# ProProject_GD32F103C8t6_2024-04-28.net
KiCad netlist of a schematic drawn in EasyEDA Pro
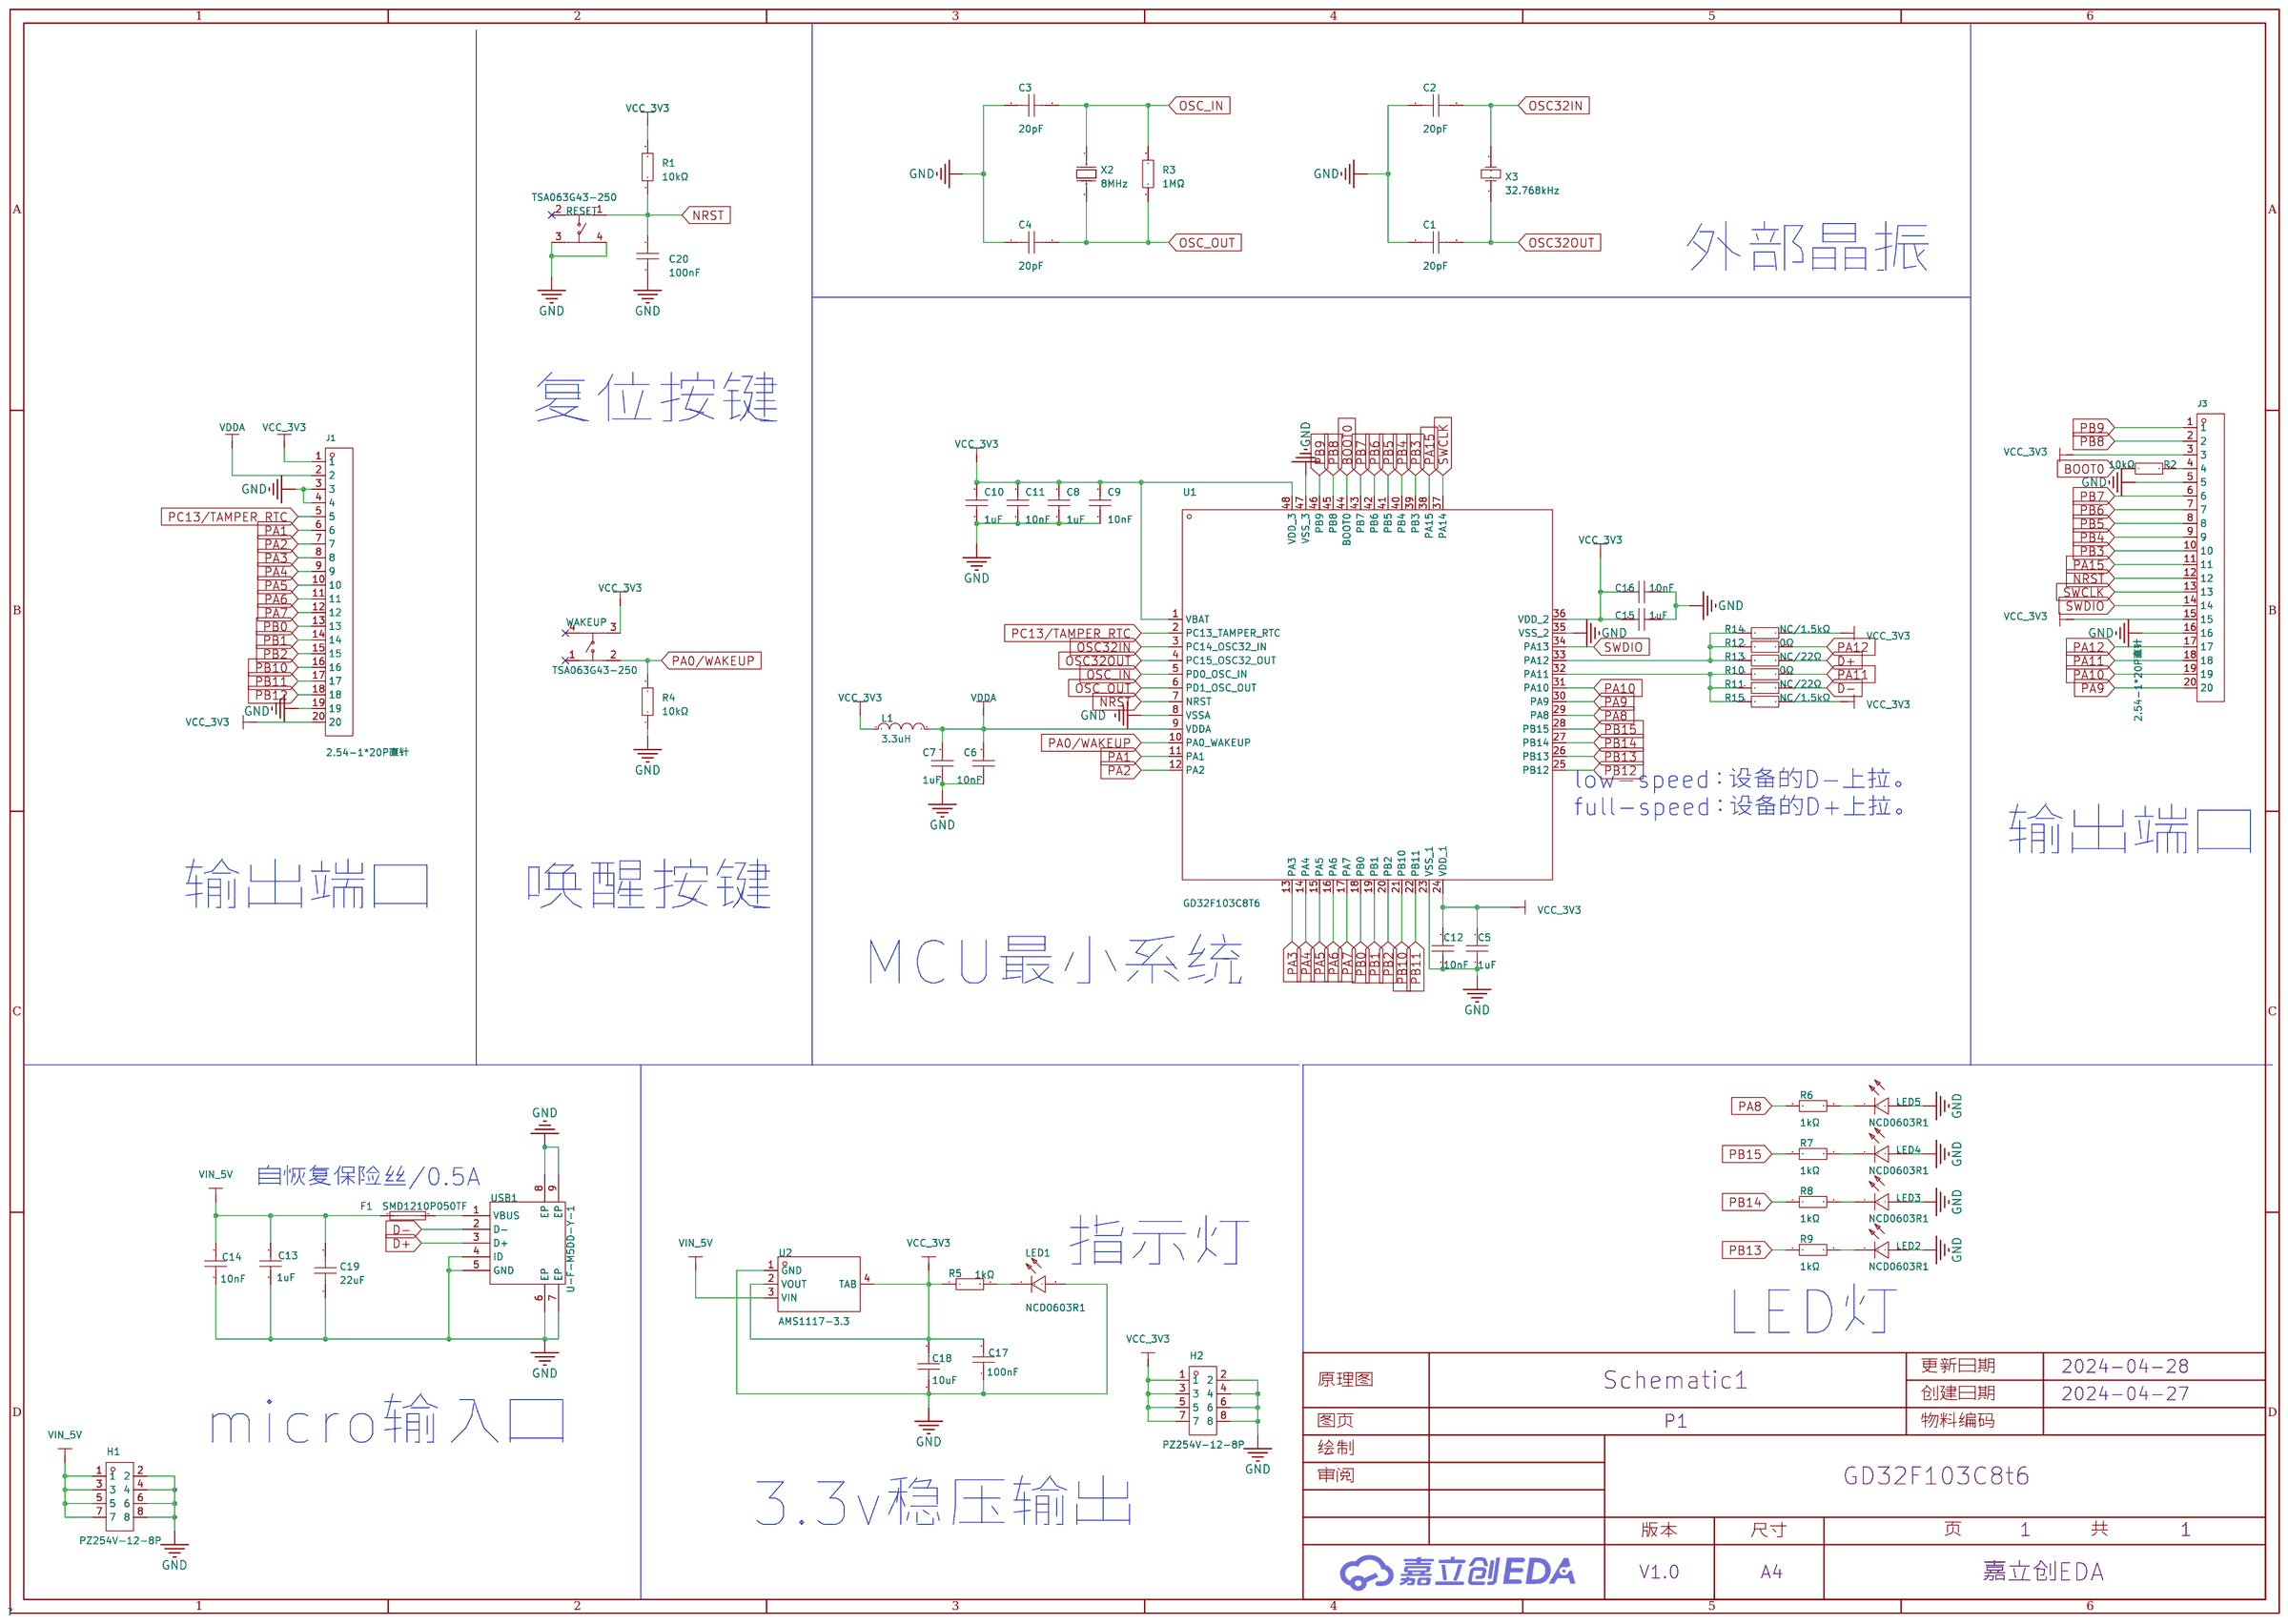
[diagram p0: schematic sheet]

(export (version "E")
  (design (tool "Eeschema 10.0.6"))
  (components
    (comp (ref "C1")
      (value "20pF")
      (footprint "easyedapro:C0603")
      (description "容值:20pF;精度:±5%;额定电压:50V;材质(温度系数):C0G;")
      (fields (field (name "Manufacturer Part") "0603CG200J500NT") (field (name "Manufacturer") "FH(风华)"))
      (libsource (lib "easyedapro") (part "0603CG200J500NT"))
    )
    (comp (ref "C2")
      (value "20pF")
      (footprint "easyedapro:C0603")
      (description "容值:20pF;精度:±5%;额定电压:50V;材质(温度系数):C0G;")
      (fields (field (name "Manufacturer Part") "0603CG200J500NT") (field (name "Manufacturer") "FH(风华)"))
      (libsource (lib "easyedapro") (part "0603CG200J500NT"))
    )
    (comp (ref "C3")
      (value "20pF")
      (footprint "easyedapro:C0603")
      (description "容值:20pF;精度:±5%;额定电压:50V;材质(温度系数):C0G;")
      (fields (field (name "Manufacturer Part") "0603CG200J500NT") (field (name "Manufacturer") "FH(风华)"))
      (libsource (lib "easyedapro") (part "0603CG200J500NT"))
    )
    (comp (ref "C4")
      (value "20pF")
      (footprint "easyedapro:C0603")
      (description "容值:20pF;精度:±5%;额定电压:50V;材质(温度系数):C0G;")
      (fields (field (name "Manufacturer Part") "0603CG200J500NT") (field (name "Manufacturer") "FH(风华)"))
      (libsource (lib "easyedapro") (part "0603CG200J500NT"))
    )
    (comp (ref "C5")
      (value "1uF")
      (footprint "easyedapro:C0603")
      (description "容值:1uF;精度:±10%;额定电压:10V;材质(温度系数):X5R;")
      (fields
        (field (name "Manufacturer Part") "CL10A105KP8NNNC")
        (field (name "Manufacturer") "SAMSUNG(三星)")
      )
      (libsource (lib "easyedapro") (part "CL10A105KP8NNNC"))
    )
    (comp (ref "C6")
      (value "10nF")
      (footprint "easyedapro:C0603")
      (description "容值:10nF;精度:±10%;额定电压:50V;材质(温度系数):X7R;")
      (fields
        (field (name "Manufacturer Part") "CC0603KRX7R9BB103")
        (field (name "Manufacturer") "YAGEO(国巨)")
      )
      (libsource (lib "easyedapro") (part "CC0603KRX7R9BB103"))
    )
    (comp (ref "C7")
      (value "1uF")
      (footprint "easyedapro:C0603")
      (description "容值:1uF;精度:±10%;额定电压:10V;材质(温度系数):X5R;")
      (fields
        (field (name "Manufacturer Part") "CL10A105KP8NNNC")
        (field (name "Manufacturer") "SAMSUNG(三星)")
      )
      (libsource (lib "easyedapro") (part "CL10A105KP8NNNC"))
    )
    (comp (ref "C8")
      (value "1uF")
      (footprint "easyedapro:C0603")
      (description "容值:1uF;精度:±10%;额定电压:10V;材质(温度系数):X5R;")
      (fields
        (field (name "Manufacturer Part") "CL10A105KP8NNNC")
        (field (name "Manufacturer") "SAMSUNG(三星)")
      )
      (libsource (lib "easyedapro") (part "CL10A105KP8NNNC"))
    )
    (comp (ref "C9")
      (value "10nF")
      (footprint "easyedapro:C0603")
      (description "容值:10nF;精度:±10%;额定电压:50V;材质(温度系数):X7R;")
      (fields
        (field (name "Manufacturer Part") "CC0603KRX7R9BB103")
        (field (name "Manufacturer") "YAGEO(国巨)")
      )
      (libsource (lib "easyedapro") (part "CC0603KRX7R9BB103"))
    )
    (comp (ref "C10")
      (value "1uF")
      (footprint "easyedapro:C0603")
      (description "容值:1uF;精度:±10%;额定电压:10V;材质(温度系数):X5R;")
      (fields
        (field (name "Manufacturer Part") "CL10A105KP8NNNC")
        (field (name "Manufacturer") "SAMSUNG(三星)")
      )
      (libsource (lib "easyedapro") (part "CL10A105KP8NNNC"))
    )
    (comp (ref "C11")
      (value "10nF")
      (footprint "easyedapro:C0603")
      (description "容值:10nF;精度:±10%;额定电压:50V;材质(温度系数):X7R;")
      (fields
        (field (name "Manufacturer Part") "CC0603KRX7R9BB103")
        (field (name "Manufacturer") "YAGEO(国巨)")
      )
      (libsource (lib "easyedapro") (part "CC0603KRX7R9BB103"))
    )
    (comp (ref "C12")
      (value "10nF")
      (footprint "easyedapro:C0603")
      (description "容值:10nF;精度:±10%;额定电压:50V;材质(温度系数):X7R;")
      (fields
        (field (name "Manufacturer Part") "CC0603KRX7R9BB103")
        (field (name "Manufacturer") "YAGEO(国巨)")
      )
      (libsource (lib "easyedapro") (part "CC0603KRX7R9BB103"))
    )
    (comp (ref "C13")
      (value "1uF")
      (footprint "easyedapro:C0603")
      (description "容值:1uF;精度:±10%;额定电压:10V;材质(温度系数):X5R;")
      (fields
        (field (name "Manufacturer Part") "CL10A105KP8NNNC")
        (field (name "Manufacturer") "SAMSUNG(三星)")
      )
      (libsource (lib "easyedapro") (part "CL10A105KP8NNNC"))
    )
    (comp (ref "C14")
      (value "10nF")
      (footprint "easyedapro:C0603")
      (description "容值:10nF;精度:±10%;额定电压:50V;材质(温度系数):X7R;")
      (fields
        (field (name "Manufacturer Part") "CC0603KRX7R9BB103")
        (field (name "Manufacturer") "YAGEO(国巨)")
      )
      (libsource (lib "easyedapro") (part "CC0603KRX7R9BB103"))
    )
    (comp (ref "C15")
      (value "1uF")
      (footprint "easyedapro:C0603")
      (description "容值:1uF;精度:±10%;额定电压:10V;材质(温度系数):X5R;")
      (fields
        (field (name "Manufacturer Part") "CL10A105KP8NNNC")
        (field (name "Manufacturer") "SAMSUNG(三星)")
      )
      (libsource (lib "easyedapro") (part "CL10A105KP8NNNC"))
    )
    (comp (ref "C16")
      (value "10nF")
      (footprint "easyedapro:C0603")
      (description "容值:10nF;精度:±10%;额定电压:50V;材质(温度系数):X7R;")
      (fields
        (field (name "Manufacturer Part") "CC0603KRX7R9BB103")
        (field (name "Manufacturer") "YAGEO(国巨)")
      )
      (libsource (lib "easyedapro") (part "CC0603KRX7R9BB103"))
    )
    (comp (ref "C17")
      (value "100nF")
      (footprint "easyedapro:C0603")
      (description "容值:100nF;精度:±10%;额定电压:50V;材质(温度系数):X7R;")
      (fields (field (name "Manufacturer Part") "0603B104K500NT") (field (name "Manufacturer") "FH(风华)"))
      (libsource (lib "easyedapro") (part "0603B104K500NT"))
    )
    (comp (ref "C18")
      (value "10uF")
      (footprint "easyedapro:C0805")
      (description "容值:10uF;精度:±10%;额定电压:25V;材质(温度系数):X5R;")
      (fields
        (field (name "Manufacturer Part") "CL21A106KAYNNNE")
        (field (name "Manufacturer") "SAMSUNG(三星)")
      )
      (libsource (lib "easyedapro") (part "CL21A106KAYNNNE"))
    )
    (comp (ref "C19")
      (value "22uF")
      (footprint "easyedapro:C0805")
      (description "容值:22uF;精度:±20%;额定电压:25V;材质(温度系数):X5R;")
      (fields
        (field (name "Manufacturer Part") "CL21A226MAQNNNE")
        (field (name "Manufacturer") "SAMSUNG(三星)")
      )
      (libsource (lib "easyedapro") (part "CL21A226MAQNNNE"))
    )
    (comp (ref "C20")
      (value "100nF")
      (footprint "easyedapro:C0603")
      (description "容值:100nF;精度:±10%;额定电压:50V;材质(温度系数):X7R;")
      (fields (field (name "Manufacturer Part") "0603B104K500NT") (field (name "Manufacturer") "FH(风华)"))
      (libsource (lib "easyedapro") (part "0603B104K500NT"))
    )
    (comp (ref "F1")
      (value "SMD1210P050TF")
      (footprint "easyedapro:F1210")
      (description "最大电压:13.2V;最大电流:100A;保持电流:500mA;跳闸电流:1A;")
      (fields (field (name "Manufacturer") "RUILON(瑞隆源)"))
      (libsource (lib "easyedapro") (part "SMD1210P050TF"))
    )
    (comp (ref "H1")
      (value "PZ254V-12-8P")
      (footprint "easyedapro:HDR-TH_8P-P2.54-V-M-R2-C4-S2.54")
      (fields (field (name "Manufacturer") "XFCN(兴飞)"))
      (libsource (lib "easyedapro") (part "PZ254V-12-8P"))
    )
    (comp (ref "H2")
      (value "PZ254V-12-8P")
      (footprint "easyedapro:HDR-TH_8P-P2.54-V-M-R2-C4-S2.54")
      (fields (field (name "Manufacturer") "XFCN(兴飞)"))
      (libsource (lib "easyedapro") (part "PZ254V-12-8P"))
    )
    (comp (ref "J1")
      (value "2.54-1*20P直针")
      (footprint "easyedapro:HDR-TH_20P-P2.54-V-M-1")
      (fields (field (name "Manufacturer") "BOOMELE(博穆精密)"))
      (libsource (lib "easyedapro") (part "Header-Male-2.54_1x20"))
    )
    (comp (ref "J3")
      (value "2.54-1*20P直针")
      (footprint "easyedapro:HDR-TH_20P-P2.54-V-M-1")
      (fields (field (name "Manufacturer") "BOOMELE(博穆精密)"))
      (libsource (lib "easyedapro") (part "Header-Male-2.54_1x20"))
    )
    (comp (ref "L1")
      (value "3.3uH")
      (footprint "easyedapro:L0603")
      (description "电感值:3.3uH;精度:±10%;额定电流:15mA;饱和电流(Isat):-;直流电阻(DCR):1Ω;")
      (fields (field (name "Manufacturer Part") "CMI160808U3R3KT") (field (name "Manufacturer") "FH(风华)"))
      (libsource (lib "easyedapro") (part "CMI160808U3R3KT"))
    )
    (comp (ref "LED1")
      (value "NCD0603R1")
      (footprint "easyedapro:LED0603-RD_RED")
      (fields (field (name "Manufacturer") "国星光电"))
      (libsource (lib "easyedapro") (part "FC-DA1608HRK-620D"))
    )
    (comp (ref "LED2")
      (value "NCD0603R1")
      (footprint "easyedapro:LED0603-RD_RED")
      (fields (field (name "Manufacturer") "国星光电"))
      (libsource (lib "easyedapro") (part "FC-DA1608HRK-620D"))
    )
    (comp (ref "LED3")
      (value "NCD0603R1")
      (footprint "easyedapro:LED0603-RD_RED")
      (fields (field (name "Manufacturer") "国星光电"))
      (libsource (lib "easyedapro") (part "FC-DA1608HRK-620D"))
    )
    (comp (ref "LED4")
      (value "NCD0603R1")
      (footprint "easyedapro:LED0603-RD_RED")
      (fields (field (name "Manufacturer") "国星光电"))
      (libsource (lib "easyedapro") (part "FC-DA1608HRK-620D"))
    )
    (comp (ref "LED5")
      (value "NCD0603R1")
      (footprint "easyedapro:LED0603-RD_RED")
      (fields (field (name "Manufacturer") "国星光电"))
      (libsource (lib "easyedapro") (part "FC-DA1608HRK-620D"))
    )
    (comp (ref "R1")
      (value "10kΩ")
      (footprint "easyedapro:R0603")
      (description "电阻类型:厚膜电阻;阻值:10kΩ;精度:±5%;功率:100mW;最大工作电压:75V;温度系数:±100ppm/°C;")
      (fields (field (name "Manufacturer Part") "RC0603JR-0710KL") (field (name "Manufacturer") "YAGEO(国巨)"))
      (libsource (lib "easyedapro") (part "RC0603JR-0710KL"))
    )
    (comp (ref "R2")
      (value "10kΩ")
      (footprint "easyedapro:R0603")
      (description "电阻类型:厚膜电阻;阻值:10kΩ;精度:±5%;功率:100mW;最大工作电压:75V;温度系数:±100ppm/°C;")
      (fields (field (name "Manufacturer Part") "RC0603JR-0710KL") (field (name "Manufacturer") "YAGEO(国巨)"))
      (libsource (lib "easyedapro") (part "RC0603JR-0710KL"))
    )
    (comp (ref "R3")
      (value "1MΩ")
      (footprint "easyedapro:R0603")
      (description "电阻类型:厚膜电阻;阻值:1MΩ;精度:±5%;功率:100mW;最大工作电压:75V;温度系数:±100ppm/°C;")
      (fields (field (name "Manufacturer Part") "RC0603JR-071ML") (field (name "Manufacturer") "YAGEO(国巨)"))
      (libsource (lib "easyedapro") (part "RC0603JR-071ML"))
    )
    (comp (ref "R4")
      (value "10kΩ")
      (footprint "easyedapro:R0603")
      (description "电阻类型:厚膜电阻;阻值:10kΩ;精度:±5%;功率:100mW;最大工作电压:75V;温度系数:±100ppm/°C;")
      (fields (field (name "Manufacturer Part") "RC0603JR-0710KL") (field (name "Manufacturer") "YAGEO(国巨)"))
      (libsource (lib "easyedapro") (part "RC0603JR-0710KL"))
    )
    (comp (ref "R5")
      (value "1kΩ")
      (footprint "easyedapro:R0603")
      (description "电阻类型:薄膜电阻;阻值:1kΩ;精度:±0.1%;功率:100mW;最大工作电压:75V;温度系数:±25ppm/°C;")
      (fields (field (name "Manufacturer Part") "RT0603BRD071KL") (field (name "Manufacturer") "YAGEO(国巨)"))
      (libsource (lib "easyedapro") (part "RT0603BRD071KL"))
    )
    (comp (ref "R6")
      (value "1kΩ")
      (footprint "easyedapro:R0603")
      (description "电阻类型:薄膜电阻;阻值:1kΩ;精度:±0.1%;功率:100mW;最大工作电压:75V;温度系数:±25ppm/°C;")
      (fields (field (name "Manufacturer Part") "RT0603BRD071KL") (field (name "Manufacturer") "YAGEO(国巨)"))
      (libsource (lib "easyedapro") (part "RT0603BRD071KL"))
    )
    (comp (ref "R7")
      (value "1kΩ")
      (footprint "easyedapro:R0603")
      (description "电阻类型:薄膜电阻;阻值:1kΩ;精度:±0.1%;功率:100mW;最大工作电压:75V;温度系数:±25ppm/°C;")
      (fields (field (name "Manufacturer Part") "RT0603BRD071KL") (field (name "Manufacturer") "YAGEO(国巨)"))
      (libsource (lib "easyedapro") (part "RT0603BRD071KL"))
    )
    (comp (ref "R8")
      (value "1kΩ")
      (footprint "easyedapro:R0603")
      (description "电阻类型:薄膜电阻;阻值:1kΩ;精度:±0.1%;功率:100mW;最大工作电压:75V;温度系数:±25ppm/°C;")
      (fields (field (name "Manufacturer Part") "RT0603BRD071KL") (field (name "Manufacturer") "YAGEO(国巨)"))
      (libsource (lib "easyedapro") (part "RT0603BRD071KL"))
    )
    (comp (ref "R9")
      (value "1kΩ")
      (footprint "easyedapro:R0603")
      (description "电阻类型:薄膜电阻;阻值:1kΩ;精度:±0.1%;功率:100mW;最大工作电压:75V;温度系数:±25ppm/°C;")
      (fields (field (name "Manufacturer Part") "RT0603BRD071KL") (field (name "Manufacturer") "YAGEO(国巨)"))
      (libsource (lib "easyedapro") (part "RT0603BRD071KL"))
    )
    (comp (ref "R10")
      (value "0Ω")
      (footprint "easyedapro:R0603")
      (description "电阻类型:厚膜电阻;阻值:1.5kΩ;精度:±1%;功率:100mW;最大工作电压:50V;温度系数:±100ppm/°C;")
      (fields
        (field (name "Manufacturer Part") "0603WAJ0000T5E")
        (field (name "Manufacturer") "UNI-ROYAL(厚声)")
      )
      (libsource (lib "easyedapro") (part "RS-03K1501FT"))
    )
    (comp (ref "R11")
      (value "NC/22Ω")
      (footprint "easyedapro:R0603")
      (description "电阻类型:厚膜电阻;阻值:22Ω;精度:±1%;功率:100mW;最大工作电压:50V;温度系数:±100ppm/°C;")
      (fields (field (name "Manufacturer Part") "RS-03K22R0FT") (field (name "Manufacturer") "FH(风华)"))
      (libsource (lib "easyedapro") (part "RS-03K22R0FT"))
    )
    (comp (ref "R12")
      (value "0Ω")
      (footprint "easyedapro:R0603")
      (description "电阻类型:厚膜电阻;阻值:1.5kΩ;精度:±1%;功率:100mW;最大工作电压:50V;温度系数:±100ppm/°C;")
      (fields
        (field (name "Manufacturer Part") "0603WAJ0000T5E")
        (field (name "Manufacturer") "UNI-ROYAL(厚声)")
      )
      (libsource (lib "easyedapro") (part "RS-03K1501FT"))
    )
    (comp (ref "R13")
      (value "NC/22Ω")
      (footprint "easyedapro:R0603")
      (description "电阻类型:厚膜电阻;阻值:22Ω;精度:±1%;功率:100mW;最大工作电压:50V;温度系数:±100ppm/°C;")
      (fields (field (name "Manufacturer Part") "RS-03K22R0FT") (field (name "Manufacturer") "FH(风华)"))
      (libsource (lib "easyedapro") (part "RS-03K22R0FT"))
    )
    (comp (ref "R14")
      (value "NC/1.5kΩ")
      (footprint "easyedapro:R0603")
      (description "电阻类型:厚膜电阻;阻值:1.5kΩ;精度:±1%;功率:100mW;最大工作电压:50V;温度系数:±100ppm/°C;")
      (fields (field (name "Manufacturer Part") "RS-03K1501FT") (field (name "Manufacturer") "FH(风华)"))
      (libsource (lib "easyedapro") (part "RS-03K1501FT"))
    )
    (comp (ref "R15")
      (value "NC/1.5kΩ")
      (footprint "easyedapro:R0603")
      (description "电阻类型:厚膜电阻;阻值:1.5kΩ;精度:±1%;功率:100mW;最大工作电压:50V;温度系数:±100ppm/°C;")
      (fields (field (name "Manufacturer Part") "RS-03K1501FT") (field (name "Manufacturer") "FH(风华)"))
      (libsource (lib "easyedapro") (part "RS-03K1501FT"))
    )
    (comp (ref "RESET")
      (value "TSA063G43-250")
      (footprint "easyedapro:KEY-SMD_4P-L6.0-W6.0-P4.50-LS10.0")
      (fields (field (name "Manufacturer") "BRIGHT(博瑞泰)"))
      (libsource (lib "easyedapro") (part "TSA063G43-250"))
    )
    (comp (ref "U1")
      (value "GD32F103C8T6")
      (footprint "easyedapro:TQFP-48_L7.0-W7.0-P0.50-LS9.0-BL")
      (description "CPU内核:CM3;程序存储容量:64KB;RAM总容量:20KB;GPIO端口数量:37;工作电压范围:2.6V~3.6V;CPU最大主频:108MHz;程序存储器类型:FLASH;")
      (fields (field (name "Manufacturer") "GigaDevice(兆易创新)"))
      (libsource (lib "easyedapro") (part "GD32F103C8T6"))
    )
    (comp (ref "U2")
      (value "AMS1117-3.3")
      (footprint "easyedapro:SOT-223-3_L6.5-W3.5-P3.05-LS7.0")
      (description "输出类型：固定 输出极性：正 最大输入电压：18V 输出电压：3.3V 输出电流：1A 电源纹波抑制比(PSRR)：60dB@(120Hz)。当前应用较多领域：三端稳压器，机顶盒")
      (fields (field (name "Manufacturer") "TWGMC(台湾迪嘉)"))
      (libsource (lib "easyedapro") (part "AMS1117-3.3_C5250992"))
    )
    (comp (ref "USB1")
      (value "U-F-M5DD-Y-1")
      (footprint "easyedapro:MICRO-USB-SMD_U-F-M5DD-Y-1")
      (description "连接器类型:Micro-B;标准:USB 2.0;公母:母;端口数量:1;触点数量:5P;额定电流 - 电源:1A;")
      (fields (field (name "Manufacturer") "韩国韩荣"))
      (libsource (lib "easyedapro") (part "U-F-M5DD-Y-1"))
    )
    (comp (ref "WAKEUP")
      (value "TSA063G43-250")
      (footprint "easyedapro:KEY-SMD_4P-L6.0-W6.0-P4.50-LS10.0")
      (fields (field (name "Manufacturer") "BRIGHT(博瑞泰)"))
      (libsource (lib "easyedapro") (part "TSA063G43-250"))
    )
    (comp (ref "X2")
      (value "8MHz")
      (footprint "easyedapro:OSC-TH_L10.0-W4.5-P5.00")
      (description "晶振类型:直插晶振;频率:8MHz;常温频差:±20ppm;外接负载电容:20pF;频率稳定度(全温):±30ppm;")
      (fields (field (name "Manufacturer Part") "X49SD8MSD2SC") (field (name "Manufacturer") "YXC(扬兴晶振)"))
      (libsource (lib "easyedapro") (part "X49SD8MSD2SC"))
    )
    (comp (ref "X3")
      (value "32.768kHz")
      (footprint "easyedapro:OSC-TH_BD3.1-P0.8-D0.3")
      (description "晶振类型:直插晶振;频率:32.768kHz;常温频差:±10ppm;外接负载电容:12.5pF;频率稳定度(全温):-;")
      (fields (field (name "Manufacturer Part") "X308032768KGB2SC") (field (name "Manufacturer") "YXC(扬兴晶振)"))
      (libsource (lib "easyedapro") (part "X308032768KGB2SC"))
    )
  )
  (nets
    (net (code "1") (name "BOOT0") (class "Default")
      (node (ref "R2") (pin "1") (pinfunction "1_1") (pintype "input"))
      (node (ref "U1") (pin "44") (pinfunction "BOOT0_44") (pintype "unspecified"))
    )
    (net (code "2") (name "D+") (class "Default")
      (node (ref "R13") (pin "2") (pinfunction "2_2") (pintype "unspecified"))
      (node (ref "USB1") (pin "3") (pinfunction "D+_3") (pintype "unspecified"))
    )
    (net (code "3") (name "D-") (class "Default")
      (node (ref "R11") (pin "2") (pinfunction "2_2") (pintype "unspecified"))
      (node (ref "USB1") (pin "2") (pinfunction "D-_2") (pintype "unspecified"))
    )
    (net (code "4") (name "GND") (class "Default")
      (node (ref "C1") (pin "1") (pinfunction "1_1") (pintype "unspecified"))
      (node (ref "C10") (pin "1") (pinfunction "1_1") (pintype "input"))
      (node (ref "C11") (pin "1") (pinfunction "1_1") (pintype "input"))
      (node (ref "C12") (pin "1") (pinfunction "1_1") (pintype "input"))
      (node (ref "C13") (pin "1") (pinfunction "1_1") (pintype "input"))
      (node (ref "C14") (pin "1") (pinfunction "1_1") (pintype "input"))
      (node (ref "C15") (pin "1") (pinfunction "1_1") (pintype "input"))
      (node (ref "C16") (pin "1") (pinfunction "1_1") (pintype "input"))
      (node (ref "C17") (pin "1") (pinfunction "1_1") (pintype "input"))
      (node (ref "C18") (pin "1") (pinfunction "1_1") (pintype "unspecified"))
      (node (ref "C19") (pin "1") (pinfunction "1_1") (pintype "unspecified"))
      (node (ref "C2") (pin "1") (pinfunction "1_1") (pintype "unspecified"))
      (node (ref "C20") (pin "1") (pinfunction "1_1") (pintype "input"))
      (node (ref "C3") (pin "1") (pinfunction "1_1") (pintype "unspecified"))
      (node (ref "C4") (pin "1") (pinfunction "1_1") (pintype "unspecified"))
      (node (ref "C5") (pin "1") (pinfunction "1_1") (pintype "input"))
      (node (ref "C6") (pin "1") (pinfunction "1_1") (pintype "input"))
      (node (ref "C7") (pin "1") (pinfunction "1_1") (pintype "input"))
      (node (ref "C8") (pin "1") (pinfunction "1_1") (pintype "input"))
      (node (ref "C9") (pin "1") (pinfunction "1_1") (pintype "input"))
      (node (ref "H1") (pin "2") (pinfunction "2_2") (pintype "unspecified"))
      (node (ref "H1") (pin "4") (pinfunction "4_4") (pintype "unspecified"))
      (node (ref "H1") (pin "6") (pinfunction "6_6") (pintype "unspecified"))
      (node (ref "H1") (pin "8") (pinfunction "8_8") (pintype "unspecified"))
      (node (ref "H2") (pin "2") (pinfunction "2_2") (pintype "unspecified"))
      (node (ref "H2") (pin "4") (pinfunction "4_4") (pintype "unspecified"))
      (node (ref "H2") (pin "6") (pinfunction "6_6") (pintype "unspecified"))
      (node (ref "H2") (pin "8") (pinfunction "8_8") (pintype "unspecified"))
      (node (ref "J1") (pin "19") (pinfunction "19_19") (pintype "input"))
      (node (ref "J1") (pin "3") (pinfunction "3_3") (pintype "input"))
      (node (ref "J1") (pin "4") (pinfunction "4_4") (pintype "input"))
      (node (ref "J3") (pin "16") (pinfunction "16_16") (pintype "input"))
      (node (ref "J3") (pin "5") (pinfunction "5_5") (pintype "input"))
      (node (ref "LED1") (pin "2") (pinfunction "A_2") (pintype "input"))
      (node (ref "LED2") (pin "2") (pinfunction "A_2") (pintype "input"))
      (node (ref "LED3") (pin "2") (pinfunction "A_2") (pintype "input"))
      (node (ref "LED4") (pin "2") (pinfunction "A_2") (pintype "input"))
      (node (ref "LED5") (pin "2") (pinfunction "A_2") (pintype "input"))
      (node (ref "R4") (pin "1") (pinfunction "1_1") (pintype "input"))
      (node (ref "RESET") (pin "3") (pinfunction "3_3") (pintype "input"))
      (node (ref "RESET") (pin "4") (pinfunction "4_4") (pintype "input"))
      (node (ref "U1") (pin "23") (pinfunction "VSS_1_23") (pintype "unspecified"))
      (node (ref "U1") (pin "35") (pinfunction "VSS_2_35") (pintype "unspecified"))
      (node (ref "U1") (pin "47") (pinfunction "VSS_3_47") (pintype "unspecified"))
      (node (ref "U1") (pin "8") (pinfunction "VSSA_8") (pintype "unspecified"))
      (node (ref "U2") (pin "1") (pinfunction "GND_1") (pintype "unspecified"))
      (node (ref "USB1") (pin "4") (pinfunction "ID_4") (pintype "unspecified"))
      (node (ref "USB1") (pin "5") (pinfunction "GND_5") (pintype "unspecified"))
      (node (ref "USB1") (pin "6") (pinfunction "EP_6") (pintype "unspecified"))
      (node (ref "USB1") (pin "7") (pinfunction "EP_7") (pintype "unspecified"))
      (node (ref "USB1") (pin "8") (pinfunction "EP_8") (pintype "unspecified"))
      (node (ref "USB1") (pin "9") (pinfunction "EP_9") (pintype "unspecified"))
    )
    (net (code "5") (name "NRST") (class "Default")
      (node (ref "C20") (pin "2") (pinfunction "2_2") (pintype "input"))
      (node (ref "J3") (pin "12") (pinfunction "12_12") (pintype "input"))
      (node (ref "R1") (pin "1") (pinfunction "1_1") (pintype "input"))
      (node (ref "RESET") (pin "1") (pinfunction "1_1") (pintype "input"))
      (node (ref "U1") (pin "7") (pinfunction "NRST_7") (pintype "unspecified"))
    )
    (net (code "6") (name "Net-(J3-Pad4)") (class "Default")
      (node (ref "J3") (pin "4") (pinfunction "4_4") (pintype "input"))
      (node (ref "R2") (pin "2") (pinfunction "2_2") (pintype "input"))
    )
    (net (code "7") (name "Net-(LED1-K)") (class "Default")
      (node (ref "LED1") (pin "1") (pinfunction "K_1") (pintype "input"))
      (node (ref "R5") (pin "2") (pinfunction "2_2") (pintype "input"))
    )
    (net (code "8") (name "Net-(LED2-K)") (class "Default")
      (node (ref "LED2") (pin "1") (pinfunction "K_1") (pintype "input"))
      (node (ref "R9") (pin "2") (pinfunction "2_2") (pintype "input"))
    )
    (net (code "9") (name "Net-(LED3-K)") (class "Default")
      (node (ref "LED3") (pin "1") (pinfunction "K_1") (pintype "input"))
      (node (ref "R8") (pin "2") (pinfunction "2_2") (pintype "input"))
    )
    (net (code "10") (name "Net-(LED4-K)") (class "Default")
      (node (ref "LED4") (pin "1") (pinfunction "K_1") (pintype "input"))
      (node (ref "R7") (pin "2") (pinfunction "2_2") (pintype "input"))
    )
    (net (code "11") (name "Net-(LED5-K)") (class "Default")
      (node (ref "LED5") (pin "1") (pinfunction "K_1") (pintype "input"))
      (node (ref "R6") (pin "2") (pinfunction "2_2") (pintype "input"))
    )
    (net (code "12") (name "Net-(U1-PA11)") (class "Default")
      (node (ref "R10") (pin "1") (pinfunction "1_1") (pintype "unspecified"))
      (node (ref "R11") (pin "1") (pinfunction "1_1") (pintype "unspecified"))
      (node (ref "R15") (pin "1") (pinfunction "1_1") (pintype "unspecified"))
      (node (ref "U1") (pin "32") (pinfunction "PA11_32") (pintype "unspecified"))
    )
    (net (code "13") (name "Net-(U1-PA12)") (class "Default")
      (node (ref "R12") (pin "1") (pinfunction "1_1") (pintype "unspecified"))
      (node (ref "R13") (pin "1") (pinfunction "1_1") (pintype "unspecified"))
      (node (ref "R14") (pin "1") (pinfunction "1_1") (pintype "unspecified"))
      (node (ref "U1") (pin "33") (pinfunction "PA12_33") (pintype "unspecified"))
    )
    (net (code "14") (name "Net-(USB1-VBUS)") (class "Default")
      (node (ref "F1") (pin "2") (pinfunction "2_2") (pintype "unspecified"))
      (node (ref "USB1") (pin "1") (pinfunction "VBUS_1") (pintype "unspecified"))
    )
    (net (code "15") (name "OSC32IN") (class "Default")
      (node (ref "C2") (pin "2") (pinfunction "2_2") (pintype "unspecified"))
      (node (ref "U1") (pin "3") (pinfunction "PC14_OSC32_IN_3") (pintype "unspecified"))
      (node (ref "X3") (pin "2") (pinfunction "OSC2_2") (pintype "unspecified"))
    )
    (net (code "16") (name "OSC32OUT") (class "Default")
      (node (ref "C1") (pin "2") (pinfunction "2_2") (pintype "unspecified"))
      (node (ref "U1") (pin "4") (pinfunction "PC15_OSC32_OUT_4") (pintype "unspecified"))
      (node (ref "X3") (pin "1") (pinfunction "OSC1_1") (pintype "unspecified"))
    )
    (net (code "17") (name "OSC_IN") (class "Default")
      (node (ref "C3") (pin "2") (pinfunction "2_2") (pintype "unspecified"))
      (node (ref "R3") (pin "2") (pinfunction "2_2") (pintype "input"))
      (node (ref "U1") (pin "5") (pinfunction "PD0_OSC_IN_5") (pintype "unspecified"))
      (node (ref "X2") (pin "1") (pinfunction "OSC1_1") (pintype "input"))
    )
    (net (code "18") (name "OSC_OUT") (class "Default")
      (node (ref "C4") (pin "2") (pinfunction "2_2") (pintype "unspecified"))
      (node (ref "R3") (pin "1") (pinfunction "1_1") (pintype "input"))
      (node (ref "U1") (pin "6") (pinfunction "PD1_OSC_OUT_6") (pintype "unspecified"))
      (node (ref "X2") (pin "2") (pinfunction "OSC2_2") (pintype "input"))
    )
    (net (code "19") (name "PA0{slash}WAKEUP") (class "Default")
      (node (ref "R4") (pin "2") (pinfunction "2_2") (pintype "input"))
      (node (ref "U1") (pin "10") (pinfunction "PA0_WAKEUP_10") (pintype "unspecified"))
      (node (ref "WAKEUP") (pin "2") (pinfunction "2_2") (pintype "input"))
    )
    (net (code "20") (name "PA1") (class "Default")
      (node (ref "J1") (pin "6") (pinfunction "6_6") (pintype "input"))
      (node (ref "U1") (pin "11") (pinfunction "PA1_11") (pintype "unspecified"))
    )
    (net (code "21") (name "PA2") (class "Default")
      (node (ref "J1") (pin "7") (pinfunction "7_7") (pintype "input"))
      (node (ref "U1") (pin "12") (pinfunction "PA2_12") (pintype "unspecified"))
    )
    (net (code "22") (name "PA3") (class "Default")
      (node (ref "J1") (pin "8") (pinfunction "8_8") (pintype "input"))
      (node (ref "U1") (pin "13") (pinfunction "PA3_13") (pintype "unspecified"))
    )
    (net (code "23") (name "PA4") (class "Default")
      (node (ref "J1") (pin "9") (pinfunction "9_9") (pintype "input"))
      (node (ref "U1") (pin "14") (pinfunction "PA4_14") (pintype "unspecified"))
    )
    (net (code "24") (name "PA5") (class "Default")
      (node (ref "J1") (pin "10") (pinfunction "10_10") (pintype "input"))
      (node (ref "U1") (pin "15") (pinfunction "PA5_15") (pintype "unspecified"))
    )
    (net (code "25") (name "PA6") (class "Default")
      (node (ref "J1") (pin "11") (pinfunction "11_11") (pintype "input"))
      (node (ref "U1") (pin "16") (pinfunction "PA6_16") (pintype "unspecified"))
    )
    (net (code "26") (name "PA7") (class "Default")
      (node (ref "J1") (pin "12") (pinfunction "12_12") (pintype "input"))
      (node (ref "U1") (pin "17") (pinfunction "PA7_17") (pintype "unspecified"))
    )
    (net (code "27") (name "PA8") (class "Default")
      (node (ref "R6") (pin "1") (pinfunction "1_1") (pintype "input"))
      (node (ref "U1") (pin "29") (pinfunction "PA8_29") (pintype "unspecified"))
    )
    (net (code "28") (name "PA9") (class "Default")
      (node (ref "J3") (pin "20") (pinfunction "20_20") (pintype "input"))
      (node (ref "U1") (pin "30") (pinfunction "PA9_30") (pintype "unspecified"))
    )
    (net (code "29") (name "PA10") (class "Default")
      (node (ref "J3") (pin "19") (pinfunction "19_19") (pintype "input"))
      (node (ref "U1") (pin "31") (pinfunction "PA10_31") (pintype "unspecified"))
    )
    (net (code "30") (name "PA11") (class "Default")
      (node (ref "J3") (pin "18") (pinfunction "18_18") (pintype "input"))
      (node (ref "R10") (pin "2") (pinfunction "2_2") (pintype "unspecified"))
    )
    (net (code "31") (name "PA12") (class "Default")
      (node (ref "J3") (pin "17") (pinfunction "17_17") (pintype "input"))
      (node (ref "R12") (pin "2") (pinfunction "2_2") (pintype "unspecified"))
    )
    (net (code "32") (name "PA15") (class "Default")
      (node (ref "J3") (pin "11") (pinfunction "11_11") (pintype "input"))
      (node (ref "U1") (pin "38") (pinfunction "PA15_38") (pintype "unspecified"))
    )
    (net (code "33") (name "PB0") (class "Default")
      (node (ref "J1") (pin "13") (pinfunction "13_13") (pintype "input"))
      (node (ref "U1") (pin "18") (pinfunction "PB0_18") (pintype "unspecified"))
    )
    (net (code "34") (name "PB1") (class "Default")
      (node (ref "J1") (pin "14") (pinfunction "14_14") (pintype "input"))
      (node (ref "U1") (pin "19") (pinfunction "PB1_19") (pintype "unspecified"))
    )
    (net (code "35") (name "PB2") (class "Default")
      (node (ref "J1") (pin "15") (pinfunction "15_15") (pintype "input"))
      (node (ref "U1") (pin "20") (pinfunction "PB2_20") (pintype "unspecified"))
    )
    (net (code "36") (name "PB3") (class "Default")
      (node (ref "J3") (pin "10") (pinfunction "10_10") (pintype "input"))
      (node (ref "U1") (pin "39") (pinfunction "PB3_39") (pintype "unspecified"))
    )
    (net (code "37") (name "PB4") (class "Default")
      (node (ref "J3") (pin "9") (pinfunction "9_9") (pintype "input"))
      (node (ref "U1") (pin "40") (pinfunction "PB4_40") (pintype "unspecified"))
    )
    (net (code "38") (name "PB5") (class "Default")
      (node (ref "J3") (pin "8") (pinfunction "8_8") (pintype "input"))
      (node (ref "U1") (pin "41") (pinfunction "PB5_41") (pintype "unspecified"))
    )
    (net (code "39") (name "PB6") (class "Default")
      (node (ref "J3") (pin "7") (pinfunction "7_7") (pintype "input"))
      (node (ref "U1") (pin "42") (pinfunction "PB6_42") (pintype "unspecified"))
    )
    (net (code "40") (name "PB7") (class "Default")
      (node (ref "J3") (pin "6") (pinfunction "6_6") (pintype "input"))
      (node (ref "U1") (pin "43") (pinfunction "PB7_43") (pintype "unspecified"))
    )
    (net (code "41") (name "PB8") (class "Default")
      (node (ref "J3") (pin "2") (pinfunction "2_2") (pintype "input"))
      (node (ref "U1") (pin "45") (pinfunction "PB8_45") (pintype "unspecified"))
    )
    (net (code "42") (name "PB9") (class "Default")
      (node (ref "J3") (pin "1") (pinfunction "1_1") (pintype "input"))
      (node (ref "U1") (pin "46") (pinfunction "PB9_46") (pintype "unspecified"))
    )
    (net (code "43") (name "PB10") (class "Default")
      (node (ref "J1") (pin "16") (pinfunction "16_16") (pintype "input"))
      (node (ref "U1") (pin "21") (pinfunction "PB10_21") (pintype "unspecified"))
    )
    (net (code "44") (name "PB11") (class "Default")
      (node (ref "J1") (pin "17") (pinfunction "17_17") (pintype "input"))
      (node (ref "U1") (pin "22") (pinfunction "PB11_22") (pintype "unspecified"))
    )
    (net (code "45") (name "PB12") (class "Default")
      (node (ref "J1") (pin "18") (pinfunction "18_18") (pintype "input"))
      (node (ref "U1") (pin "25") (pinfunction "PB12_25") (pintype "unspecified"))
    )
    (net (code "46") (name "PB13") (class "Default")
      (node (ref "R9") (pin "1") (pinfunction "1_1") (pintype "input"))
      (node (ref "U1") (pin "26") (pinfunction "PB13_26") (pintype "unspecified"))
    )
    (net (code "47") (name "PB14") (class "Default")
      (node (ref "R8") (pin "1") (pinfunction "1_1") (pintype "input"))
      (node (ref "U1") (pin "27") (pinfunction "PB14_27") (pintype "unspecified"))
    )
    (net (code "48") (name "PB15") (class "Default")
      (node (ref "R7") (pin "1") (pinfunction "1_1") (pintype "input"))
      (node (ref "U1") (pin "28") (pinfunction "PB15_28") (pintype "unspecified"))
    )
    (net (code "49") (name "PC13{slash}TAMPER_RTC") (class "Default")
      (node (ref "J1") (pin "5") (pinfunction "5_5") (pintype "input"))
      (node (ref "U1") (pin "2") (pinfunction "PC13_TAMPER_RTC_2") (pintype "unspecified"))
    )
    (net (code "50") (name "SWCLK") (class "Default")
      (node (ref "J3") (pin "13") (pinfunction "13_13") (pintype "input"))
      (node (ref "U1") (pin "37") (pinfunction "PA14_37") (pintype "unspecified"))
    )
    (net (code "51") (name "SWDIO") (class "Default")
      (node (ref "J3") (pin "14") (pinfunction "14_14") (pintype "input"))
      (node (ref "U1") (pin "34") (pinfunction "PA13_34") (pintype "unspecified"))
    )
    (net (code "52") (name "VCC_3V3") (class "Default")
      (node (ref "C10") (pin "2") (pinfunction "2_2") (pintype "input"))
      (node (ref "C11") (pin "2") (pinfunction "2_2") (pintype "input"))
      (node (ref "C12") (pin "2") (pinfunction "2_2") (pintype "input"))
      (node (ref "C15") (pin "2") (pinfunction "2_2") (pintype "input"))
      (node (ref "C16") (pin "2") (pinfunction "2_2") (pintype "input"))
      (node (ref "C17") (pin "2") (pinfunction "2_2") (pintype "input"))
      (node (ref "C18") (pin "2") (pinfunction "2_2") (pintype "unspecified"))
      (node (ref "C5") (pin "2") (pinfunction "2_2") (pintype "input"))
      (node (ref "C8") (pin "2") (pinfunction "2_2") (pintype "input"))
      (node (ref "C9") (pin "2") (pinfunction "2_2") (pintype "input"))
      (node (ref "H2") (pin "1") (pinfunction "1_1") (pintype "unspecified"))
      (node (ref "H2") (pin "3") (pinfunction "3_3") (pintype "unspecified"))
      (node (ref "H2") (pin "5") (pinfunction "5_5") (pintype "unspecified"))
      (node (ref "H2") (pin "7") (pinfunction "7_7") (pintype "unspecified"))
      (node (ref "J1") (pin "1") (pinfunction "1_1") (pintype "input"))
      (node (ref "J1") (pin "20") (pinfunction "20_20") (pintype "input"))
      (node (ref "J3") (pin "15") (pinfunction "15_15") (pintype "input"))
      (node (ref "J3") (pin "3") (pinfunction "3_3") (pintype "input"))
      (node (ref "L1") (pin "1") (pinfunction "1_1") (pintype "unspecified"))
      (node (ref "R1") (pin "2") (pinfunction "2_2") (pintype "input"))
      (node (ref "R14") (pin "2") (pinfunction "2_2") (pintype "unspecified"))
      (node (ref "R15") (pin "2") (pinfunction "2_2") (pintype "unspecified"))
      (node (ref "R5") (pin "1") (pinfunction "1_1") (pintype "input"))
      (node (ref "U1") (pin "1") (pinfunction "VBAT_1") (pintype "unspecified"))
      (node (ref "U1") (pin "24") (pinfunction "VDD_1_24") (pintype "unspecified"))
      (node (ref "U1") (pin "36") (pinfunction "VDD_2_36") (pintype "unspecified"))
      (node (ref "U1") (pin "48") (pinfunction "VDD_3_48") (pintype "unspecified"))
      (node (ref "U2") (pin "2") (pinfunction "VOUT_2") (pintype "unspecified"))
      (node (ref "U2") (pin "4") (pinfunction "TAB_4") (pintype "unspecified"))
      (node (ref "WAKEUP") (pin "3") (pinfunction "3_3") (pintype "input"))
    )
    (net (code "53") (name "VDDA") (class "Default")
      (node (ref "C6") (pin "2") (pinfunction "2_2") (pintype "input"))
      (node (ref "C7") (pin "2") (pinfunction "2_2") (pintype "input"))
      (node (ref "J1") (pin "2") (pinfunction "2_2") (pintype "input"))
      (node (ref "L1") (pin "2") (pinfunction "2_2") (pintype "unspecified"))
      (node (ref "U1") (pin "9") (pinfunction "VDDA_9") (pintype "unspecified"))
    )
    (net (code "54") (name "VIN_5V") (class "Default")
      (node (ref "C13") (pin "2") (pinfunction "2_2") (pintype "input"))
      (node (ref "C14") (pin "2") (pinfunction "2_2") (pintype "input"))
      (node (ref "C19") (pin "2") (pinfunction "2_2") (pintype "unspecified"))
      (node (ref "F1") (pin "1") (pinfunction "1_1") (pintype "unspecified"))
      (node (ref "H1") (pin "1") (pinfunction "1_1") (pintype "unspecified"))
      (node (ref "H1") (pin "3") (pinfunction "3_3") (pintype "unspecified"))
      (node (ref "H1") (pin "5") (pinfunction "5_5") (pintype "unspecified"))
      (node (ref "H1") (pin "7") (pinfunction "7_7") (pintype "unspecified"))
      (node (ref "U2") (pin "3") (pinfunction "VIN_3") (pintype "unspecified"))
    )
    (net (code "55") (name "unconnected-(RESET-Pad2)") (class "Default")
      (node (ref "RESET") (pin "2") (pinfunction "2_2") (pintype "input+no_connect"))
    )
    (net (code "56") (name "unconnected-(WAKEUP-Pad1)") (class "Default")
      (node (ref "WAKEUP") (pin "1") (pinfunction "1_1") (pintype "input+no_connect"))
    )
    (net (code "57") (name "unconnected-(WAKEUP-Pad4)") (class "Default")
      (node (ref "WAKEUP") (pin "4") (pinfunction "4_4") (pintype "input+no_connect"))
    )
  )
)
